# Sheet2.net
KiCad netlist of a schematic drawn in Altium Designer
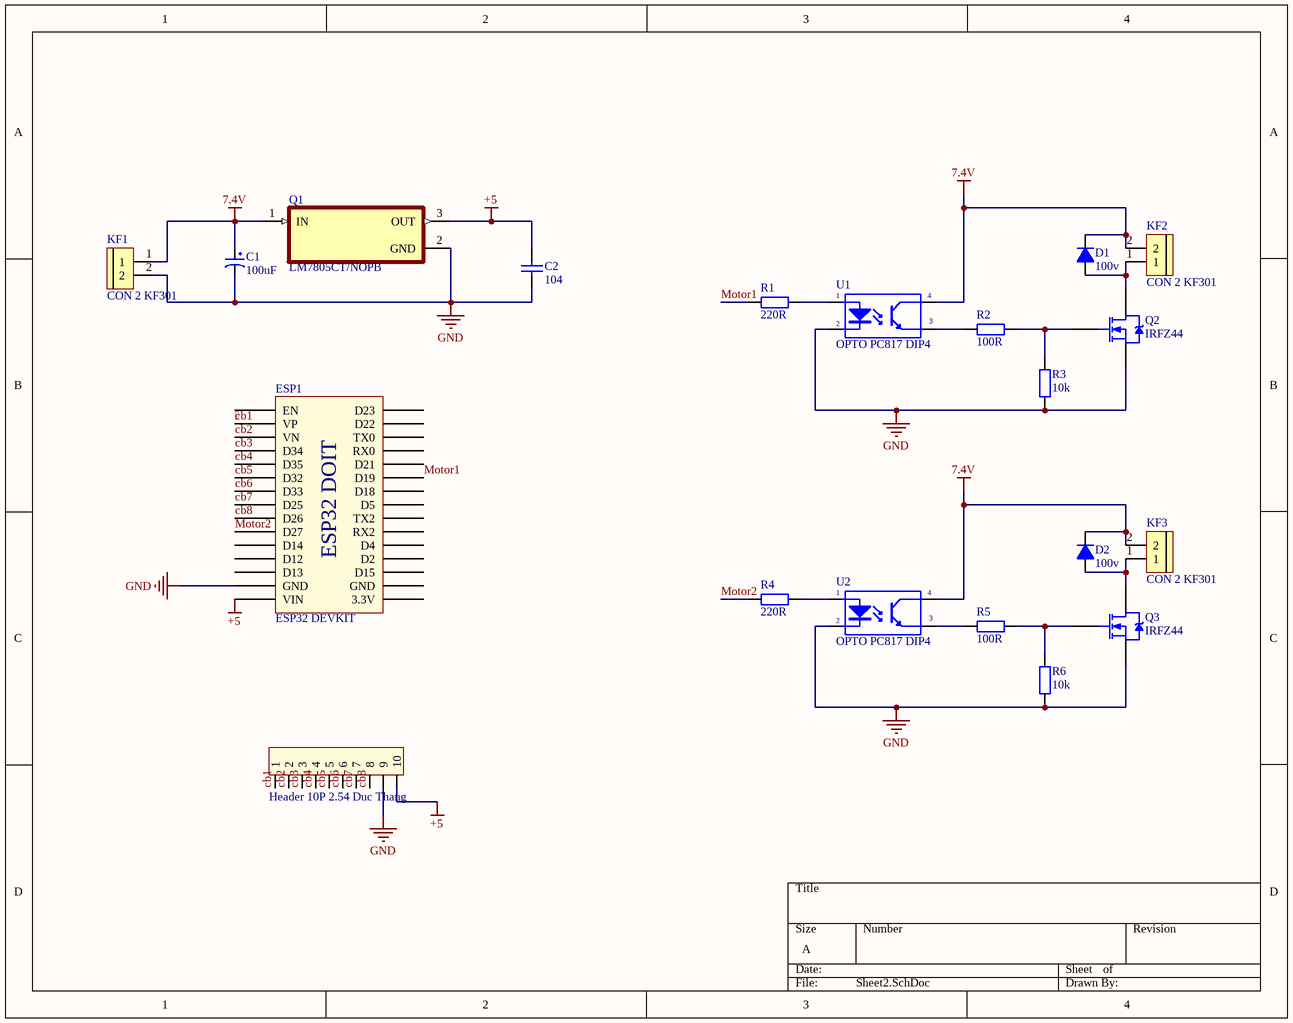
[diagram p0: Sheet2.SchDoc]

(export (version "E")
  (design (tool "Eeschema 10.0.6"))
  (components
    (comp (ref "C1")
      (value "100uF")
      (footprint "tu hoa 5mm")
      (description "Cắm")
      (libsource (lib "Capacitor") (part "Tu Hoa 100uF 16V 5x7"))
    )
    (comp (ref "C2")
      (value "104")
      (footprint "tu gom")
      (description "Cắm")
      (libsource (lib "Capacitor") (part "Tu gom 104 50V"))
    )
    (comp (ref "D1")
      (value "100v")
      (footprint "DIODE 1A")
      (description "Cắm")
      (libsource (lib "Diode") (part "Diode 1N4007"))
    )
    (comp (ref "D2")
      (value "100v")
      (footprint "DIODE 1A")
      (description "Cắm")
      (libsource (lib "Diode") (part "Diode 1N4007"))
    )
    (comp (ref "ESP1")
      (value "ESP32 DEVKIT")
      (footprint "ESP32 WROOM 32 KIT")
      (libsource (lib "Module") (part "ESP32 WROOM 32 KIT"))
    )
    (comp (ref "H1")
      (value "Header 10P 2.54 Duc Thang")
      (footprint "XH2.54M-10")
      (description "Cắm")
      (libsource (lib "Header") (part "Header 10P 2.54 Duc Thang"))
    )
    (comp (ref "KF1")
      (value "CON 2 KF301")
      (footprint "Con 2 KF301 5.08")
      (description "Cắm")
      (libsource (lib "") (part "CON 2 KF301_1"))
    )
    (comp (ref "KF2")
      (value "CON 2 KF301")
      (footprint "Con 2 KF301 5.08")
      (description "Cắm")
      (libsource (lib "Connector") (part "CON 2 KF301"))
    )
    (comp (ref "KF3")
      (value "CON 2 KF301")
      (footprint "Con 2 KF301 5.08")
      (description "Cắm")
      (libsource (lib "Connector") (part "CON 2 KF301"))
    )
    (comp (ref "Q1")
      (value "LM7805CT/NOPB")
      (footprint "TO254P1054X470X1955-3")
      (fields (field (name "MF") "{'manufacturer': u'Texas Instruments'}"))
      (libsource (lib "LM7805CT_NOPB") (part "LM7805CT/NOPB"))
    )
    (comp (ref "Q2")
      (value "IRFZ44")
      (footprint "TO220")
      (description "TO-220")
      (libsource (lib "TranFet") (part "FET IRFZ44 DIP"))
    )
    (comp (ref "Q3")
      (value "IRFZ44")
      (footprint "TO220")
      (description "TO-220")
      (libsource (lib "TranFet") (part "FET IRFZ44 DIP"))
    )
    (comp (ref "R1")
      (value "220R")
      (footprint "tro vach 1/4w")
      (description "Cắm")
      (libsource (lib "Resistor") (part "Tro Vach 1/4W 5% 220R"))
    )
    (comp (ref "R2")
      (value "100R")
      (footprint "tro vach 1/4w")
      (description "Cắm")
      (libsource (lib "Resistor") (part "Tro Vach 1/4W 5% 100R"))
    )
    (comp (ref "R3")
      (value "10k")
      (footprint "tro vach 1/4w")
      (description "Cắm")
      (libsource (lib "Resistor") (part "Tro Vach 1/4W 1% 10k"))
    )
    (comp (ref "R4")
      (value "220R")
      (footprint "tro vach 1/4w")
      (description "Cắm")
      (libsource (lib "Resistor") (part "Tro Vach 1/4W 5% 220R"))
    )
    (comp (ref "R5")
      (value "100R")
      (footprint "tro vach 1/4w")
      (description "Cắm")
      (libsource (lib "Resistor") (part "Tro Vach 1/4W 5% 100R"))
    )
    (comp (ref "R6")
      (value "10k")
      (footprint "tro vach 1/4w")
      (description "Cắm")
      (libsource (lib "Resistor") (part "Tro Vach 1/4W 1% 10k"))
    )
    (comp (ref "U1")
      (value "OPTO PC817 DIP4")
      (footprint "DIP4")
      (description "Single Opto")
      (libsource (lib "IC") (part "OPTO PC817 DIP4"))
    )
    (comp (ref "U2")
      (value "OPTO PC817 DIP4")
      (footprint "DIP4")
      (description "Single Opto")
      (libsource (lib "IC") (part "OPTO PC817 DIP4"))
    )
  )
  (nets
    (net (code "1") (name "+5") (class "Default")
      (node (ref "C2") (pin "1") (pinfunction "1_1") (pintype "passive"))
      (node (ref "ESP1") (pin "15") (pinfunction "VIN_15") (pintype "passive"))
      (node (ref "H1") (pin "10") (pinfunction "10_10") (pintype "passive"))
      (node (ref "Q1") (pin "3") (pinfunction "OUT_3") (pintype "output"))
    )
    (net (code "2") (name "/") (class "Default")
      (node (ref "ESP1") (pin "2") (pinfunction "VP_2") (pintype "passive"))
      (node (ref "H1") (pin "1") (pinfunction "1_1") (pintype "passive"))
    )
    (net (code "3") (name "/Motor1") (class "Default")
      (node (ref "ESP1") (pin "25") (pinfunction "D19_25") (pintype "passive"))
      (node (ref "R1") (pin "1") (pinfunction "1_1") (pintype "passive"))
    )
    (net (code "4") (name "/Motor2") (class "Default")
      (node (ref "ESP1") (pin "10") (pinfunction "D27_10") (pintype "passive"))
      (node (ref "R4") (pin "1") (pinfunction "1_1") (pintype "passive"))
    )
    (net (code "5") (name "/cb2") (class "Default")
      (node (ref "ESP1") (pin "3") (pinfunction "VN_3") (pintype "passive"))
      (node (ref "H1") (pin "2") (pinfunction "2_2") (pintype "passive"))
    )
    (net (code "6") (name "/cb3") (class "Default")
      (node (ref "ESP1") (pin "4") (pinfunction "D34_4") (pintype "passive"))
      (node (ref "H1") (pin "3") (pinfunction "3_3") (pintype "passive"))
    )
    (net (code "7") (name "/cb4") (class "Default")
      (node (ref "ESP1") (pin "5") (pinfunction "D35_5") (pintype "passive"))
      (node (ref "H1") (pin "4") (pinfunction "4_4") (pintype "passive"))
    )
    (net (code "8") (name "/cb5") (class "Default")
      (node (ref "ESP1") (pin "6") (pinfunction "D32_6") (pintype "passive"))
      (node (ref "H1") (pin "5") (pinfunction "5_5") (pintype "passive"))
    )
    (net (code "9") (name "/cb6") (class "Default")
      (node (ref "ESP1") (pin "7") (pinfunction "D33_7") (pintype "passive"))
      (node (ref "H1") (pin "6") (pinfunction "6_6") (pintype "passive"))
    )
    (net (code "10") (name "/cb7") (class "Default")
      (node (ref "ESP1") (pin "8") (pinfunction "D25_8") (pintype "passive"))
      (node (ref "H1") (pin "7") (pinfunction "7_7") (pintype "passive"))
    )
    (net (code "11") (name "/cb8") (class "Default")
      (node (ref "ESP1") (pin "9") (pinfunction "D26_9") (pintype "passive"))
      (node (ref "H1") (pin "8") (pinfunction "8_8") (pintype "passive"))
    )
    (net (code "12") (name "7.4V") (class "Default")
      (node (ref "C1") (pin "1") (pinfunction "1_1") (pintype "passive"))
      (node (ref "D1") (pin "2") (pinfunction "K_2") (pintype "passive"))
      (node (ref "D2") (pin "2") (pinfunction "K_2") (pintype "passive"))
      (node (ref "KF1") (pin "1") (pinfunction "1_1") (pintype "passive"))
      (node (ref "KF2") (pin "2") (pinfunction "2_2") (pintype "passive"))
      (node (ref "KF3") (pin "2") (pinfunction "2_2") (pintype "passive"))
      (node (ref "Q1") (pin "1") (pinfunction "IN_1") (pintype "input"))
      (node (ref "U1") (pin "4") (pinfunction "C_4") (pintype "passive"))
      (node (ref "U2") (pin "4") (pinfunction "C_4") (pintype "passive"))
    )
    (net (code "13") (name "GND") (class "Default")
      (node (ref "C1") (pin "2") (pinfunction "2_2") (pintype "passive"))
      (node (ref "C2") (pin "2") (pinfunction "2_2") (pintype "passive"))
      (node (ref "ESP1") (pin "14") (pinfunction "GND_14") (pintype "passive"))
      (node (ref "H1") (pin "9") (pinfunction "9_9") (pintype "passive"))
      (node (ref "KF1") (pin "2") (pinfunction "2_2") (pintype "passive"))
      (node (ref "Q1") (pin "2") (pinfunction "GND_2") (pintype "power_in"))
      (node (ref "Q2") (pin "3") (pinfunction "S_3") (pintype "passive"))
      (node (ref "Q3") (pin "3") (pinfunction "S_3") (pintype "passive"))
      (node (ref "R3") (pin "1") (pinfunction "1_1") (pintype "passive"))
      (node (ref "R6") (pin "1") (pinfunction "1_1") (pintype "passive"))
      (node (ref "U1") (pin "2") (pinfunction "K_2") (pintype "passive"))
      (node (ref "U2") (pin "2") (pinfunction "K_2") (pintype "passive"))
    )
    (net (code "14") (name "Net-(D1-A)") (class "Default")
      (node (ref "D1") (pin "1") (pinfunction "A_1") (pintype "passive"))
      (node (ref "KF2") (pin "1") (pinfunction "1_1") (pintype "passive"))
      (node (ref "Q2") (pin "2") (pinfunction "D_2") (pintype "passive"))
    )
    (net (code "15") (name "Net-(D2-A)") (class "Default")
      (node (ref "D2") (pin "1") (pinfunction "A_1") (pintype "passive"))
      (node (ref "KF3") (pin "1") (pinfunction "1_1") (pintype "passive"))
      (node (ref "Q3") (pin "2") (pinfunction "D_2") (pintype "passive"))
    )
    (net (code "16") (name "Net-(Q2-G)") (class "Default")
      (node (ref "Q2") (pin "1") (pinfunction "G_1") (pintype "passive"))
      (node (ref "R2") (pin "2") (pinfunction "2_2") (pintype "passive"))
      (node (ref "R3") (pin "2") (pinfunction "2_2") (pintype "passive"))
    )
    (net (code "17") (name "Net-(Q3-G)") (class "Default")
      (node (ref "Q3") (pin "1") (pinfunction "G_1") (pintype "passive"))
      (node (ref "R5") (pin "2") (pinfunction "2_2") (pintype "passive"))
      (node (ref "R6") (pin "2") (pinfunction "2_2") (pintype "passive"))
    )
    (net (code "18") (name "Net-(U1-A)") (class "Default")
      (node (ref "R1") (pin "2") (pinfunction "2_2") (pintype "passive"))
      (node (ref "U1") (pin "1") (pinfunction "A_1") (pintype "passive"))
    )
    (net (code "19") (name "Net-(U1-E)") (class "Default")
      (node (ref "R2") (pin "1") (pinfunction "1_1") (pintype "passive"))
      (node (ref "U1") (pin "3") (pinfunction "E_3") (pintype "passive"))
    )
    (net (code "20") (name "Net-(U2-A)") (class "Default")
      (node (ref "R4") (pin "2") (pinfunction "2_2") (pintype "passive"))
      (node (ref "U2") (pin "1") (pinfunction "A_1") (pintype "passive"))
    )
    (net (code "21") (name "Net-(U2-E)") (class "Default")
      (node (ref "R5") (pin "1") (pinfunction "1_1") (pintype "passive"))
      (node (ref "U2") (pin "3") (pinfunction "E_3") (pintype "passive"))
    )
    (net (code "22") (name "unconnected-(ESP1-3.3V-Pad16)") (class "Default")
      (node (ref "ESP1") (pin "16") (pinfunction "3.3V_16") (pintype "passive"))
    )
    (net (code "23") (name "unconnected-(ESP1-D2-Pad19)") (class "Default")
      (node (ref "ESP1") (pin "19") (pinfunction "D2_19") (pintype "passive"))
    )
    (net (code "24") (name "unconnected-(ESP1-D4-Pad20)") (class "Default")
      (node (ref "ESP1") (pin "20") (pinfunction "D4_20") (pintype "passive"))
    )
    (net (code "25") (name "unconnected-(ESP1-D5-Pad23)") (class "Default")
      (node (ref "ESP1") (pin "23") (pinfunction "D5_23") (pintype "passive"))
    )
    (net (code "26") (name "unconnected-(ESP1-D12-Pad12)") (class "Default")
      (node (ref "ESP1") (pin "12") (pinfunction "D12_12") (pintype "passive"))
    )
    (net (code "27") (name "unconnected-(ESP1-D13-Pad13)") (class "Default")
      (node (ref "ESP1") (pin "13") (pinfunction "D13_13") (pintype "passive"))
    )
    (net (code "28") (name "unconnected-(ESP1-D14-Pad11)") (class "Default")
      (node (ref "ESP1") (pin "11") (pinfunction "D14_11") (pintype "passive"))
    )
    (net (code "29") (name "unconnected-(ESP1-D15-Pad18)") (class "Default")
      (node (ref "ESP1") (pin "18") (pinfunction "D15_18") (pintype "passive"))
    )
    (net (code "30") (name "unconnected-(ESP1-D18-Pad24)") (class "Default")
      (node (ref "ESP1") (pin "24") (pinfunction "D18_24") (pintype "passive"))
    )
    (net (code "31") (name "unconnected-(ESP1-D21-Pad26)") (class "Default")
      (node (ref "ESP1") (pin "26") (pinfunction "D21_26") (pintype "passive"))
    )
    (net (code "32") (name "unconnected-(ESP1-D22-Pad29)") (class "Default")
      (node (ref "ESP1") (pin "29") (pinfunction "D22_29") (pintype "passive"))
    )
    (net (code "33") (name "unconnected-(ESP1-D23-Pad30)") (class "Default")
      (node (ref "ESP1") (pin "30") (pinfunction "D23_30") (pintype "passive"))
    )
    (net (code "34") (name "unconnected-(ESP1-EN-Pad1)") (class "Default")
      (node (ref "ESP1") (pin "1") (pinfunction "EN_1") (pintype "passive"))
    )
    (net (code "35") (name "unconnected-(ESP1-GND-Pad17)") (class "Default")
      (node (ref "ESP1") (pin "17") (pinfunction "GND_17") (pintype "passive"))
    )
    (net (code "36") (name "unconnected-(ESP1-RX0-Pad27)") (class "Default")
      (node (ref "ESP1") (pin "27") (pinfunction "RX0_27") (pintype "passive"))
    )
    (net (code "37") (name "unconnected-(ESP1-RX2-Pad21)") (class "Default")
      (node (ref "ESP1") (pin "21") (pinfunction "RX2_21") (pintype "passive"))
    )
    (net (code "38") (name "unconnected-(ESP1-TX0-Pad28)") (class "Default")
      (node (ref "ESP1") (pin "28") (pinfunction "TX0_28") (pintype "passive"))
    )
    (net (code "39") (name "unconnected-(ESP1-TX2-Pad22)") (class "Default")
      (node (ref "ESP1") (pin "22") (pinfunction "TX2_22") (pintype "passive"))
    )
  )
)
